# wifi-carrier.net
KiCad netlist of a schematic drawn in EAGLE
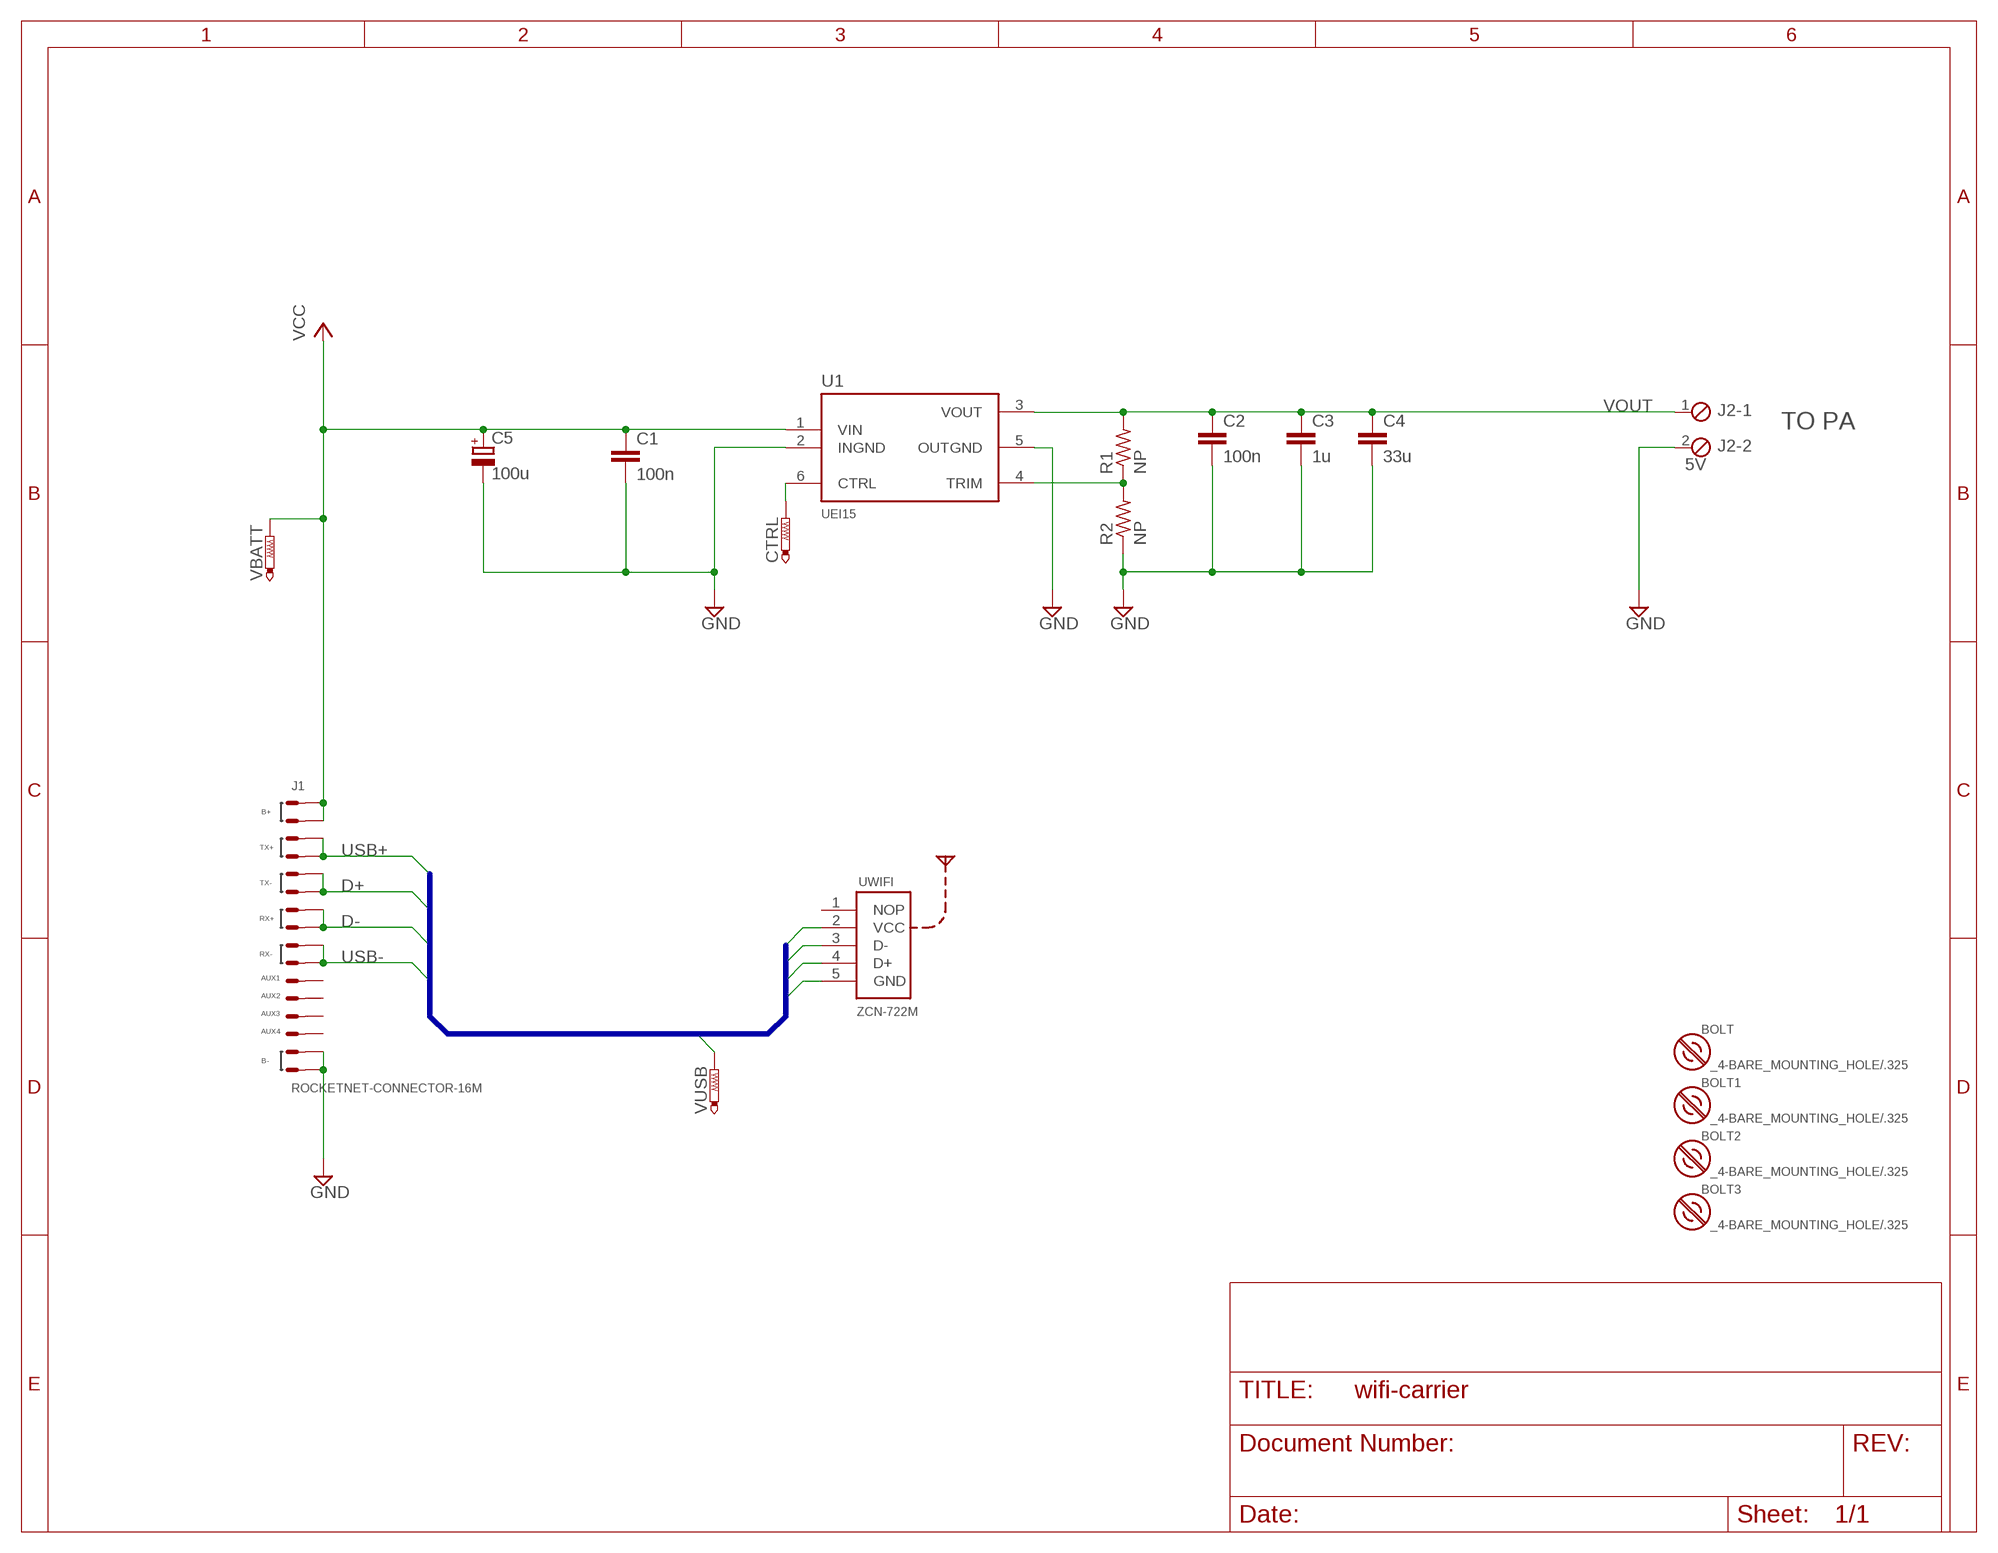
[diagram p0: schematic, sheet 1]

(export (version "E")
  (design (tool "Eeschema 10.0.6"))
  (components
    (comp (ref "BOLT")
      (value "_4-BARE_MOUNTING_HOLE/.325")
      (footprint "eagle-import:_4_.325-BARE+SMALL_TOOL_CLEARANCE")
      (libsource (lib "eagle-import") (part "_4-BARE_MOUNTING_HOLE/.325"))
    )
    (comp (ref "BOLT1")
      (value "_4-BARE_MOUNTING_HOLE/.325")
      (footprint "eagle-import:_4_.325-BARE+SMALL_TOOL_CLEARANCE")
      (libsource (lib "eagle-import") (part "_4-BARE_MOUNTING_HOLE/.325"))
    )
    (comp (ref "BOLT2")
      (value "_4-BARE_MOUNTING_HOLE/.325")
      (footprint "eagle-import:_4_.325-BARE+SMALL_TOOL_CLEARANCE")
      (libsource (lib "eagle-import") (part "_4-BARE_MOUNTING_HOLE/.325"))
    )
    (comp (ref "BOLT3")
      (value "_4-BARE_MOUNTING_HOLE/.325")
      (footprint "eagle-import:_4_.325-BARE+SMALL_TOOL_CLEARANCE")
      (libsource (lib "eagle-import") (part "_4-BARE_MOUNTING_HOLE/.325"))
    )
    (comp (ref "C1")
      (value "100n")
      (footprint "eagle-import:C0603")
      (libsource (lib "eagle-import") (part "C-EUC0603"))
    )
    (comp (ref "C2")
      (value "100n")
      (footprint "eagle-import:C0603")
      (libsource (lib "eagle-import") (part "C-EUC0603"))
    )
    (comp (ref "C3")
      (value "1u")
      (footprint "eagle-import:C0805")
      (libsource (lib "eagle-import") (part "C-EUC0805"))
    )
    (comp (ref "C4")
      (value "33u")
      (footprint "eagle-import:C1206")
      (libsource (lib "eagle-import") (part "C-EUC1206"))
    )
    (comp (ref "C5")
      (value "100u")
      (footprint "eagle-import:7660")
      (libsource (lib "eagle-import") (part "C-POL-7660"))
    )
    (comp (ref "CTRL")
      (value "PTR1PAD1-13")
      (footprint "eagle-import:P1-13")
      (libsource (lib "eagle-import") (part "PTR1PAD1-13"))
    )
    (comp (ref "J1")
      (value "ROCKETNET-CONNECTOR-16M")
      (footprint "eagle-import:ROCKETNET-M-16")
      (libsource (lib "eagle-import") (part "ROCKETNET-CONNECTOR-16M"))
    )
    (comp (ref "J2")
      (value "5V")
      (footprint "eagle-import:2POL254")
      (libsource (lib "eagle-import") (part "MPT2"))
    )
    (comp (ref "R1")
      (value "NP")
      (footprint "eagle-import:R0603")
      (libsource (lib "eagle-import") (part "R-US_R0603"))
    )
    (comp (ref "R2")
      (value "NP")
      (footprint "eagle-import:R0603")
      (libsource (lib "eagle-import") (part "R-US_R0603"))
    )
    (comp (ref "U1")
      (value "UEI15")
      (footprint "eagle-import:UEI15_PIN")
      (libsource (lib "eagle-import") (part "UEI15"))
    )
    (comp (ref "UWIFI")
      (value "ZCN-722M")
      (footprint "eagle-import:ZCN-722M")
      (libsource (lib "eagle-import") (part "ZCN-722M"))
    )
    (comp (ref "VBATT")
      (value "PTR1PAD1-13")
      (footprint "eagle-import:P1-13")
      (libsource (lib "eagle-import") (part "PTR1PAD1-13"))
    )
    (comp (ref "VUSB")
      (value "PTR1PAD1-13")
      (footprint "eagle-import:P1-13")
      (libsource (lib "eagle-import") (part "PTR1PAD1-13"))
    )
  )
  (nets
    (net (code "1") (name "/D+") (class "Default")
      (node (ref "J1") (pin "T-@11") (pinfunction "TX-_T-@11") (pintype "passive"))
      (node (ref "J1") (pin "T-@9") (pinfunction "TX-_T-@9") (pintype "passive"))
      (node (ref "UWIFI") (pin "4") (pinfunction "D+_4") (pintype "bidirectional"))
    )
    (net (code "2") (name "/D-") (class "Default")
      (node (ref "J1") (pin "R+@5") (pinfunction "RX+_R+@5") (pintype "passive"))
      (node (ref "J1") (pin "R+@7") (pinfunction "RX+_R+@7") (pintype "passive"))
      (node (ref "UWIFI") (pin "3") (pinfunction "D-_3") (pintype "bidirectional"))
    )
    (net (code "3") (name "/USB+") (class "Default")
      (node (ref "J1") (pin "T+@13") (pinfunction "TX+_T+@13") (pintype "passive"))
      (node (ref "J1") (pin "T+@14") (pinfunction "TX+_T+@14") (pintype "passive"))
      (node (ref "UWIFI") (pin "2") (pinfunction "VCC_2") (pintype "bidirectional"))
      (node (ref "VUSB") (pin "TP") (pinfunction "TP_TP") (pintype "input"))
    )
    (net (code "4") (name "/USB-") (class "Default")
      (node (ref "J1") (pin "R-@3") (pinfunction "RX-_R-@3") (pintype "passive"))
      (node (ref "J1") (pin "R-@4") (pinfunction "RX-_R-@4") (pintype "passive"))
      (node (ref "UWIFI") (pin "5") (pinfunction "GND_5") (pintype "bidirectional"))
    )
    (net (code "5") (name "/VOUT") (class "Default")
      (node (ref "C2") (pin "1") (pinfunction "1_1") (pintype "passive"))
      (node (ref "C3") (pin "1") (pinfunction "1_1") (pintype "passive"))
      (node (ref "C4") (pin "1") (pinfunction "1_1") (pintype "passive"))
      (node (ref "J2") (pin "1") (pinfunction "1_1") (pintype "passive"))
      (node (ref "R1") (pin "2") (pinfunction "2_2") (pintype "passive"))
      (node (ref "U1") (pin "3") (pinfunction "VOUT_3") (pintype "bidirectional"))
    )
    (net (code "6") (name "GND") (class "Default")
      (node (ref "C1") (pin "2") (pinfunction "2_2") (pintype "passive"))
      (node (ref "C2") (pin "2") (pinfunction "2_2") (pintype "passive"))
      (node (ref "C3") (pin "2") (pinfunction "2_2") (pintype "passive"))
      (node (ref "C4") (pin "2") (pinfunction "2_2") (pintype "passive"))
      (node (ref "C5") (pin "-") (pinfunction "-_-") (pintype "passive"))
      (node (ref "J1") (pin "B-@1") (pinfunction "B-_B-@1") (pintype "power_in"))
      (node (ref "J1") (pin "B-@2") (pinfunction "B-_B-@2") (pintype "power_in"))
      (node (ref "J2") (pin "2") (pinfunction "1_2") (pintype "passive"))
      (node (ref "R2") (pin "1") (pinfunction "1_1") (pintype "passive"))
      (node (ref "U1") (pin "2") (pinfunction "INGND_2") (pintype "bidirectional"))
      (node (ref "U1") (pin "5") (pinfunction "OUTGND_5") (pintype "bidirectional"))
    )
    (net (code "7") (name "Net-(U1-CTRL)") (class "Default")
      (node (ref "CTRL") (pin "TP") (pinfunction "TP_TP") (pintype "input"))
      (node (ref "U1") (pin "6") (pinfunction "CTRL_6") (pintype "bidirectional"))
    )
    (net (code "8") (name "Net-(U1-TRIM)") (class "Default")
      (node (ref "R1") (pin "1") (pinfunction "1_1") (pintype "passive"))
      (node (ref "R2") (pin "2") (pinfunction "2_2") (pintype "passive"))
      (node (ref "U1") (pin "4") (pinfunction "TRIM_4") (pintype "bidirectional"))
    )
    (net (code "9") (name "VCC") (class "Default")
      (node (ref "C1") (pin "1") (pinfunction "1_1") (pintype "passive"))
      (node (ref "C5") (pin "+") (pinfunction "+_+") (pintype "passive"))
      (node (ref "J1") (pin "B+@15") (pinfunction "B+_B+@15") (pintype "power_in"))
      (node (ref "J1") (pin "B+@16") (pinfunction "B+_B+@16") (pintype "power_in"))
      (node (ref "U1") (pin "1") (pinfunction "VIN_1") (pintype "bidirectional"))
      (node (ref "VBATT") (pin "TP") (pinfunction "TP_TP") (pintype "input"))
    )
    (net (code "10") (name "unconnected-(J1-AUX1-PadA1)") (class "Default")
      (node (ref "J1") (pin "A1") (pinfunction "AUX1_A1") (pintype "passive"))
    )
    (net (code "11") (name "unconnected-(J1-AUX2-PadA2)") (class "Default")
      (node (ref "J1") (pin "A2") (pinfunction "AUX2_A2") (pintype "passive"))
    )
    (net (code "12") (name "unconnected-(J1-AUX3-PadA3)") (class "Default")
      (node (ref "J1") (pin "A3") (pinfunction "AUX3_A3") (pintype "passive"))
    )
    (net (code "13") (name "unconnected-(J1-AUX4-PadA4)") (class "Default")
      (node (ref "J1") (pin "A4") (pinfunction "AUX4_A4") (pintype "passive"))
    )
    (net (code "14") (name "unconnected-(UWIFI-NOP-Pad1)") (class "Default")
      (node (ref "UWIFI") (pin "1") (pinfunction "NOP_1") (pintype "bidirectional"))
    )
  )
)
